# LED_s_Teclado2.net
KiCad netlist of a schematic drawn in Altium Designer
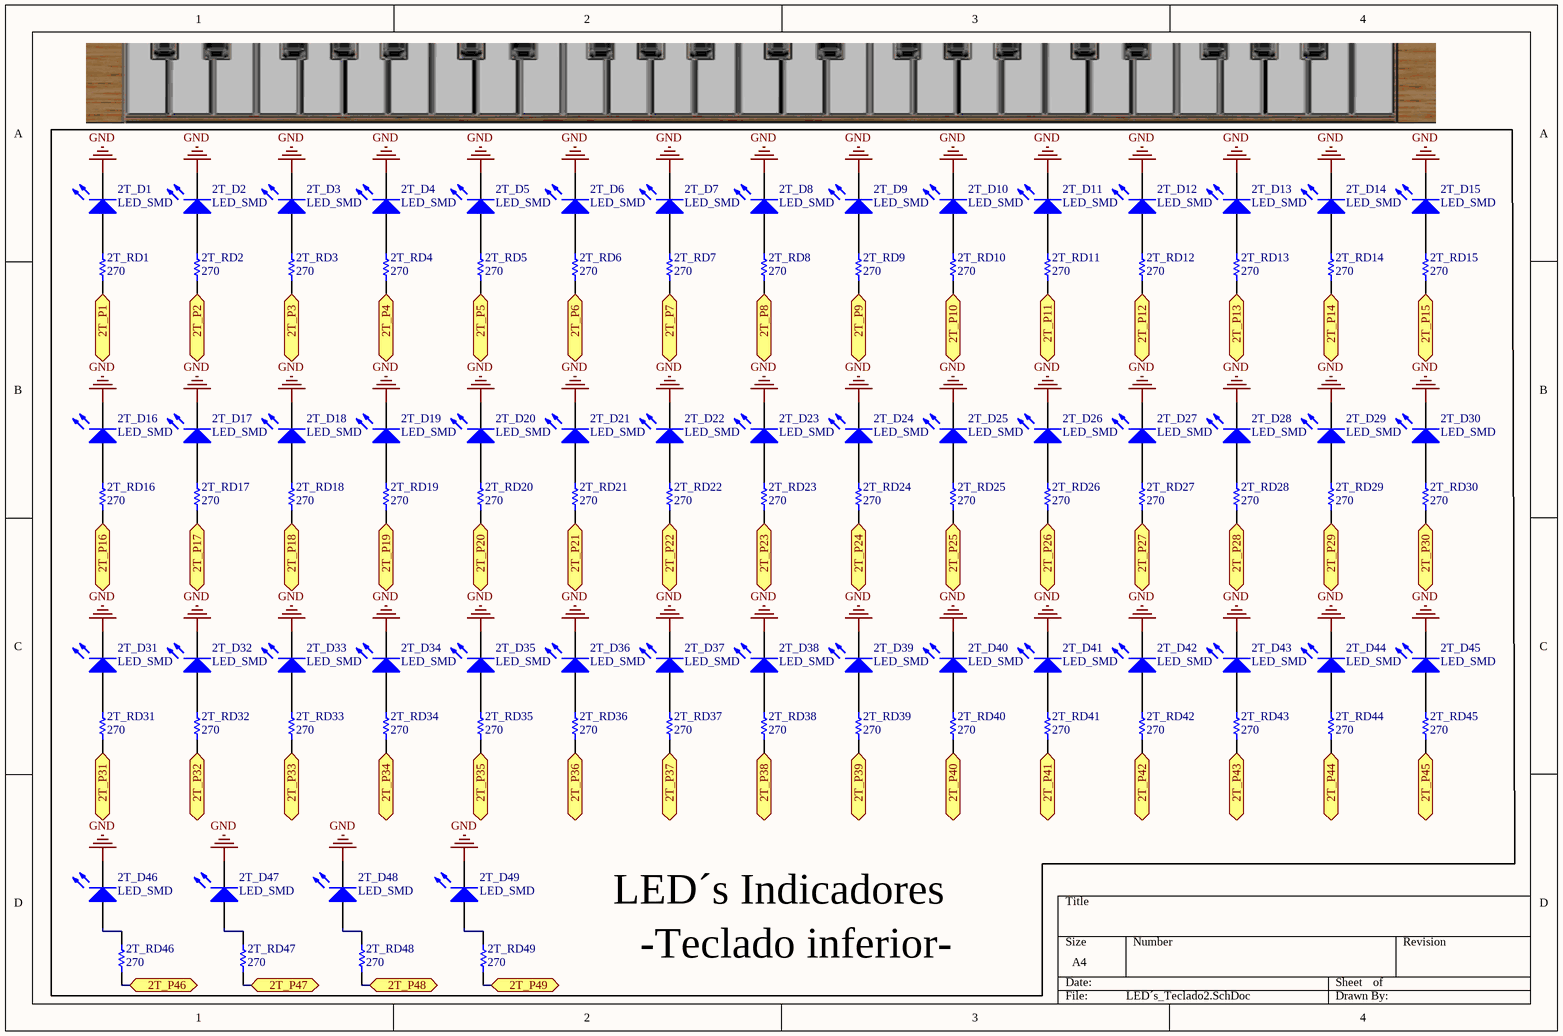
[diagram p0: LED´s_Teclado2.SchDoc]

(export (version "E")
  (design (tool "Eeschema 10.0.6"))
  (components
    (comp (ref "2T_D1")
      (value "LED_SMD")
      (footprint "0805")
      (description "LED SMD")
      (fields (field (name "PUBLISHER") "Altium Limited"))
      (libsource (lib "Libreria_Organo") (part "LED_SMD"))
    )
    (comp (ref "2T_D2")
      (value "LED_SMD")
      (footprint "0805")
      (description "LED SMD")
      (fields (field (name "PUBLISHER") "Altium Limited"))
      (libsource (lib "Libreria_Organo") (part "LED_SMD"))
    )
    (comp (ref "2T_D3")
      (value "LED_SMD")
      (footprint "0805")
      (description "LED SMD")
      (fields (field (name "PUBLISHER") "Altium Limited"))
      (libsource (lib "Libreria_Organo") (part "LED_SMD"))
    )
    (comp (ref "2T_D4")
      (value "LED_SMD")
      (footprint "0805")
      (description "LED SMD")
      (fields (field (name "PUBLISHER") "Altium Limited"))
      (libsource (lib "Libreria_Organo") (part "LED_SMD"))
    )
    (comp (ref "2T_D5")
      (value "LED_SMD")
      (footprint "0805")
      (description "LED SMD")
      (fields (field (name "PUBLISHER") "Altium Limited"))
      (libsource (lib "Libreria_Organo") (part "LED_SMD"))
    )
    (comp (ref "2T_D6")
      (value "LED_SMD")
      (footprint "0805")
      (description "LED SMD")
      (fields (field (name "PUBLISHER") "Altium Limited"))
      (libsource (lib "Libreria_Organo") (part "LED_SMD"))
    )
    (comp (ref "2T_D7")
      (value "LED_SMD")
      (footprint "0805")
      (description "LED SMD")
      (fields (field (name "PUBLISHER") "Altium Limited"))
      (libsource (lib "Libreria_Organo") (part "LED_SMD"))
    )
    (comp (ref "2T_D8")
      (value "LED_SMD")
      (footprint "0805")
      (description "LED SMD")
      (fields (field (name "PUBLISHER") "Altium Limited"))
      (libsource (lib "Libreria_Organo") (part "LED_SMD"))
    )
    (comp (ref "2T_D9")
      (value "LED_SMD")
      (footprint "0805")
      (description "LED SMD")
      (fields (field (name "PUBLISHER") "Altium Limited"))
      (libsource (lib "Libreria_Organo") (part "LED_SMD"))
    )
    (comp (ref "2T_D10")
      (value "LED_SMD")
      (footprint "0805")
      (description "LED SMD")
      (fields (field (name "PUBLISHER") "Altium Limited"))
      (libsource (lib "Libreria_Organo") (part "LED_SMD"))
    )
    (comp (ref "2T_D11")
      (value "LED_SMD")
      (footprint "0805")
      (description "LED SMD")
      (fields (field (name "PUBLISHER") "Altium Limited"))
      (libsource (lib "Libreria_Organo") (part "LED_SMD"))
    )
    (comp (ref "2T_D12")
      (value "LED_SMD")
      (footprint "0805")
      (description "LED SMD")
      (fields (field (name "PUBLISHER") "Altium Limited"))
      (libsource (lib "Libreria_Organo") (part "LED_SMD"))
    )
    (comp (ref "2T_D13")
      (value "LED_SMD")
      (footprint "0805")
      (description "LED SMD")
      (fields (field (name "PUBLISHER") "Altium Limited"))
      (libsource (lib "Libreria_Organo") (part "LED_SMD"))
    )
    (comp (ref "2T_D14")
      (value "LED_SMD")
      (footprint "0805")
      (description "LED SMD")
      (fields (field (name "PUBLISHER") "Altium Limited"))
      (libsource (lib "Libreria_Organo") (part "LED_SMD"))
    )
    (comp (ref "2T_D15")
      (value "LED_SMD")
      (footprint "0805")
      (description "LED SMD")
      (fields (field (name "PUBLISHER") "Altium Limited"))
      (libsource (lib "Libreria_Organo") (part "LED_SMD"))
    )
    (comp (ref "2T_D16")
      (value "LED_SMD")
      (footprint "0805")
      (description "LED SMD")
      (fields (field (name "PUBLISHER") "Altium Limited"))
      (libsource (lib "Libreria_Organo") (part "LED_SMD"))
    )
    (comp (ref "2T_D17")
      (value "LED_SMD")
      (footprint "0805")
      (description "LED SMD")
      (fields (field (name "PUBLISHER") "Altium Limited"))
      (libsource (lib "Libreria_Organo") (part "LED_SMD"))
    )
    (comp (ref "2T_D18")
      (value "LED_SMD")
      (footprint "0805")
      (description "LED SMD")
      (fields (field (name "PUBLISHER") "Altium Limited"))
      (libsource (lib "Libreria_Organo") (part "LED_SMD"))
    )
    (comp (ref "2T_D19")
      (value "LED_SMD")
      (footprint "0805")
      (description "LED SMD")
      (fields (field (name "PUBLISHER") "Altium Limited"))
      (libsource (lib "Libreria_Organo") (part "LED_SMD"))
    )
    (comp (ref "2T_D20")
      (value "LED_SMD")
      (footprint "0805")
      (description "LED SMD")
      (fields (field (name "PUBLISHER") "Altium Limited"))
      (libsource (lib "Libreria_Organo") (part "LED_SMD"))
    )
    (comp (ref "2T_D21")
      (value "LED_SMD")
      (footprint "0805")
      (description "LED SMD")
      (fields (field (name "PUBLISHER") "Altium Limited"))
      (libsource (lib "Libreria_Organo") (part "LED_SMD"))
    )
    (comp (ref "2T_D22")
      (value "LED_SMD")
      (footprint "0805")
      (description "LED SMD")
      (fields (field (name "PUBLISHER") "Altium Limited"))
      (libsource (lib "Libreria_Organo") (part "LED_SMD"))
    )
    (comp (ref "2T_D23")
      (value "LED_SMD")
      (footprint "0805")
      (description "LED SMD")
      (fields (field (name "PUBLISHER") "Altium Limited"))
      (libsource (lib "Libreria_Organo") (part "LED_SMD"))
    )
    (comp (ref "2T_D24")
      (value "LED_SMD")
      (footprint "0805")
      (description "LED SMD")
      (fields (field (name "PUBLISHER") "Altium Limited"))
      (libsource (lib "Libreria_Organo") (part "LED_SMD"))
    )
    (comp (ref "2T_D25")
      (value "LED_SMD")
      (footprint "0805")
      (description "LED SMD")
      (fields (field (name "PUBLISHER") "Altium Limited"))
      (libsource (lib "Libreria_Organo") (part "LED_SMD"))
    )
    (comp (ref "2T_D26")
      (value "LED_SMD")
      (footprint "0805")
      (description "LED SMD")
      (fields (field (name "PUBLISHER") "Altium Limited"))
      (libsource (lib "Libreria_Organo") (part "LED_SMD"))
    )
    (comp (ref "2T_D27")
      (value "LED_SMD")
      (footprint "0805")
      (description "LED SMD")
      (fields (field (name "PUBLISHER") "Altium Limited"))
      (libsource (lib "Libreria_Organo") (part "LED_SMD"))
    )
    (comp (ref "2T_D28")
      (value "LED_SMD")
      (footprint "0805")
      (description "LED SMD")
      (fields (field (name "PUBLISHER") "Altium Limited"))
      (libsource (lib "Libreria_Organo") (part "LED_SMD"))
    )
    (comp (ref "2T_D29")
      (value "LED_SMD")
      (footprint "0805")
      (description "LED SMD")
      (fields (field (name "PUBLISHER") "Altium Limited"))
      (libsource (lib "Libreria_Organo") (part "LED_SMD"))
    )
    (comp (ref "2T_D30")
      (value "LED_SMD")
      (footprint "0805")
      (description "LED SMD")
      (fields (field (name "PUBLISHER") "Altium Limited"))
      (libsource (lib "Libreria_Organo") (part "LED_SMD"))
    )
    (comp (ref "2T_D31")
      (value "LED_SMD")
      (footprint "0805")
      (description "LED SMD")
      (fields (field (name "PUBLISHER") "Altium Limited"))
      (libsource (lib "Libreria_Organo") (part "LED_SMD"))
    )
    (comp (ref "2T_D32")
      (value "LED_SMD")
      (footprint "0805")
      (description "LED SMD")
      (fields (field (name "PUBLISHER") "Altium Limited"))
      (libsource (lib "Libreria_Organo") (part "LED_SMD"))
    )
    (comp (ref "2T_D33")
      (value "LED_SMD")
      (footprint "0805")
      (description "LED SMD")
      (fields (field (name "PUBLISHER") "Altium Limited"))
      (libsource (lib "Libreria_Organo") (part "LED_SMD"))
    )
    (comp (ref "2T_D34")
      (value "LED_SMD")
      (footprint "0805")
      (description "LED SMD")
      (fields (field (name "PUBLISHER") "Altium Limited"))
      (libsource (lib "Libreria_Organo") (part "LED_SMD"))
    )
    (comp (ref "2T_D35")
      (value "LED_SMD")
      (footprint "0805")
      (description "LED SMD")
      (fields (field (name "PUBLISHER") "Altium Limited"))
      (libsource (lib "Libreria_Organo") (part "LED_SMD"))
    )
    (comp (ref "2T_D36")
      (value "LED_SMD")
      (footprint "0805")
      (description "LED SMD")
      (fields (field (name "PUBLISHER") "Altium Limited"))
      (libsource (lib "Libreria_Organo") (part "LED_SMD"))
    )
    (comp (ref "2T_D37")
      (value "LED_SMD")
      (footprint "0805")
      (description "LED SMD")
      (fields (field (name "PUBLISHER") "Altium Limited"))
      (libsource (lib "Libreria_Organo") (part "LED_SMD"))
    )
    (comp (ref "2T_D38")
      (value "LED_SMD")
      (footprint "0805")
      (description "LED SMD")
      (fields (field (name "PUBLISHER") "Altium Limited"))
      (libsource (lib "Libreria_Organo") (part "LED_SMD"))
    )
    (comp (ref "2T_D39")
      (value "LED_SMD")
      (footprint "0805")
      (description "LED SMD")
      (fields (field (name "PUBLISHER") "Altium Limited"))
      (libsource (lib "Libreria_Organo") (part "LED_SMD"))
    )
    (comp (ref "2T_D40")
      (value "LED_SMD")
      (footprint "0805")
      (description "LED SMD")
      (fields (field (name "PUBLISHER") "Altium Limited"))
      (libsource (lib "Libreria_Organo") (part "LED_SMD"))
    )
    (comp (ref "2T_D41")
      (value "LED_SMD")
      (footprint "0805")
      (description "LED SMD")
      (fields (field (name "PUBLISHER") "Altium Limited"))
      (libsource (lib "Libreria_Organo") (part "LED_SMD"))
    )
    (comp (ref "2T_D42")
      (value "LED_SMD")
      (footprint "0805")
      (description "LED SMD")
      (fields (field (name "PUBLISHER") "Altium Limited"))
      (libsource (lib "Libreria_Organo") (part "LED_SMD"))
    )
    (comp (ref "2T_D43")
      (value "LED_SMD")
      (footprint "0805")
      (description "LED SMD")
      (fields (field (name "PUBLISHER") "Altium Limited"))
      (libsource (lib "Libreria_Organo") (part "LED_SMD"))
    )
    (comp (ref "2T_D44")
      (value "LED_SMD")
      (footprint "0805")
      (description "LED SMD")
      (fields (field (name "PUBLISHER") "Altium Limited"))
      (libsource (lib "Libreria_Organo") (part "LED_SMD"))
    )
    (comp (ref "2T_D45")
      (value "LED_SMD")
      (footprint "0805")
      (description "LED SMD")
      (fields (field (name "PUBLISHER") "Altium Limited"))
      (libsource (lib "Libreria_Organo") (part "LED_SMD"))
    )
    (comp (ref "2T_D46")
      (value "LED_SMD")
      (footprint "0805")
      (description "LED SMD")
      (fields (field (name "PUBLISHER") "Altium Limited"))
      (libsource (lib "Libreria_Organo") (part "LED_SMD"))
    )
    (comp (ref "2T_D47")
      (value "LED_SMD")
      (footprint "0805")
      (description "LED SMD")
      (fields (field (name "PUBLISHER") "Altium Limited"))
      (libsource (lib "Libreria_Organo") (part "LED_SMD"))
    )
    (comp (ref "2T_D48")
      (value "LED_SMD")
      (footprint "0805")
      (description "LED SMD")
      (fields (field (name "PUBLISHER") "Altium Limited"))
      (libsource (lib "Libreria_Organo") (part "LED_SMD"))
    )
    (comp (ref "2T_D49")
      (value "LED_SMD")
      (footprint "0805")
      (description "LED SMD")
      (fields (field (name "PUBLISHER") "Altium Limited"))
      (libsource (lib "Libreria_Organo") (part "LED_SMD"))
    )
    (comp (ref "2T_RD1")
      (value "270")
      (footprint "0805 Chip Res")
      (description "Res Chip 0805")
      (fields (field (name "PUBLISHER") "Altium Limited"))
      (libsource (lib "Libreria_Organo") (part "Resistencia"))
    )
    (comp (ref "2T_RD2")
      (value "270")
      (footprint "0805 Chip Res")
      (description "Res Chip 0805")
      (fields (field (name "PUBLISHER") "Altium Limited"))
      (libsource (lib "Libreria_Organo") (part "Resistencia"))
    )
    (comp (ref "2T_RD3")
      (value "270")
      (footprint "0805 Chip Res")
      (description "Res Chip 0805")
      (fields (field (name "PUBLISHER") "Altium Limited"))
      (libsource (lib "Libreria_Organo") (part "Resistencia"))
    )
    (comp (ref "2T_RD4")
      (value "270")
      (footprint "0805 Chip Res")
      (description "Res Chip 0805")
      (fields (field (name "PUBLISHER") "Altium Limited"))
      (libsource (lib "Libreria_Organo") (part "Resistencia"))
    )
    (comp (ref "2T_RD5")
      (value "270")
      (footprint "0805 Chip Res")
      (description "Res Chip 0805")
      (fields (field (name "PUBLISHER") "Altium Limited"))
      (libsource (lib "Libreria_Organo") (part "Resistencia"))
    )
    (comp (ref "2T_RD6")
      (value "270")
      (footprint "0805 Chip Res")
      (description "Res Chip 0805")
      (fields (field (name "PUBLISHER") "Altium Limited"))
      (libsource (lib "Libreria_Organo") (part "Resistencia"))
    )
    (comp (ref "2T_RD7")
      (value "270")
      (footprint "0805 Chip Res")
      (description "Res Chip 0805")
      (fields (field (name "PUBLISHER") "Altium Limited"))
      (libsource (lib "Libreria_Organo") (part "Resistencia"))
    )
    (comp (ref "2T_RD8")
      (value "270")
      (footprint "0805 Chip Res")
      (description "Res Chip 0805")
      (fields (field (name "PUBLISHER") "Altium Limited"))
      (libsource (lib "Libreria_Organo") (part "Resistencia"))
    )
    (comp (ref "2T_RD9")
      (value "270")
      (footprint "0805 Chip Res")
      (description "Res Chip 0805")
      (fields (field (name "PUBLISHER") "Altium Limited"))
      (libsource (lib "Libreria_Organo") (part "Resistencia"))
    )
    (comp (ref "2T_RD10")
      (value "270")
      (footprint "0805 Chip Res")
      (description "Res Chip 0805")
      (fields (field (name "PUBLISHER") "Altium Limited"))
      (libsource (lib "Libreria_Organo") (part "Resistencia"))
    )
    (comp (ref "2T_RD11")
      (value "270")
      (footprint "0805 Chip Res")
      (description "Res Chip 0805")
      (fields (field (name "PUBLISHER") "Altium Limited"))
      (libsource (lib "Libreria_Organo") (part "Resistencia"))
    )
    (comp (ref "2T_RD12")
      (value "270")
      (footprint "0805 Chip Res")
      (description "Res Chip 0805")
      (fields (field (name "PUBLISHER") "Altium Limited"))
      (libsource (lib "Libreria_Organo") (part "Resistencia"))
    )
    (comp (ref "2T_RD13")
      (value "270")
      (footprint "0805 Chip Res")
      (description "Res Chip 0805")
      (fields (field (name "PUBLISHER") "Altium Limited"))
      (libsource (lib "Libreria_Organo") (part "Resistencia"))
    )
    (comp (ref "2T_RD14")
      (value "270")
      (footprint "0805 Chip Res")
      (description "Res Chip 0805")
      (fields (field (name "PUBLISHER") "Altium Limited"))
      (libsource (lib "Libreria_Organo") (part "Resistencia"))
    )
    (comp (ref "2T_RD15")
      (value "270")
      (footprint "0805 Chip Res")
      (description "Res Chip 0805")
      (fields (field (name "PUBLISHER") "Altium Limited"))
      (libsource (lib "Libreria_Organo") (part "Resistencia"))
    )
    (comp (ref "2T_RD16")
      (value "270")
      (footprint "0805 Chip Res")
      (description "Res Chip 0805")
      (fields (field (name "PUBLISHER") "Altium Limited"))
      (libsource (lib "Libreria_Organo") (part "Resistencia"))
    )
    (comp (ref "2T_RD17")
      (value "270")
      (footprint "0805 Chip Res")
      (description "Res Chip 0805")
      (fields (field (name "PUBLISHER") "Altium Limited"))
      (libsource (lib "Libreria_Organo") (part "Resistencia"))
    )
    (comp (ref "2T_RD18")
      (value "270")
      (footprint "0805 Chip Res")
      (description "Res Chip 0805")
      (fields (field (name "PUBLISHER") "Altium Limited"))
      (libsource (lib "Libreria_Organo") (part "Resistencia"))
    )
    (comp (ref "2T_RD19")
      (value "270")
      (footprint "0805 Chip Res")
      (description "Res Chip 0805")
      (fields (field (name "PUBLISHER") "Altium Limited"))
      (libsource (lib "Libreria_Organo") (part "Resistencia"))
    )
    (comp (ref "2T_RD20")
      (value "270")
      (footprint "0805 Chip Res")
      (description "Res Chip 0805")
      (fields (field (name "PUBLISHER") "Altium Limited"))
      (libsource (lib "Libreria_Organo") (part "Resistencia"))
    )
    (comp (ref "2T_RD21")
      (value "270")
      (footprint "0805 Chip Res")
      (description "Res Chip 0805")
      (fields (field (name "PUBLISHER") "Altium Limited"))
      (libsource (lib "Libreria_Organo") (part "Resistencia"))
    )
    (comp (ref "2T_RD22")
      (value "270")
      (footprint "0805 Chip Res")
      (description "Res Chip 0805")
      (fields (field (name "PUBLISHER") "Altium Limited"))
      (libsource (lib "Libreria_Organo") (part "Resistencia"))
    )
    (comp (ref "2T_RD23")
      (value "270")
      (footprint "0805 Chip Res")
      (description "Res Chip 0805")
      (fields (field (name "PUBLISHER") "Altium Limited"))
      (libsource (lib "Libreria_Organo") (part "Resistencia"))
    )
    (comp (ref "2T_RD24")
      (value "270")
      (footprint "0805 Chip Res")
      (description "Res Chip 0805")
      (fields (field (name "PUBLISHER") "Altium Limited"))
      (libsource (lib "Libreria_Organo") (part "Resistencia"))
    )
    (comp (ref "2T_RD25")
      (value "270")
      (footprint "0805 Chip Res")
      (description "Res Chip 0805")
      (fields (field (name "PUBLISHER") "Altium Limited"))
      (libsource (lib "Libreria_Organo") (part "Resistencia"))
    )
    (comp (ref "2T_RD26")
      (value "270")
      (footprint "0805 Chip Res")
      (description "Res Chip 0805")
      (fields (field (name "PUBLISHER") "Altium Limited"))
      (libsource (lib "Libreria_Organo") (part "Resistencia"))
    )
    (comp (ref "2T_RD27")
      (value "270")
      (footprint "0805 Chip Res")
      (description "Res Chip 0805")
      (fields (field (name "PUBLISHER") "Altium Limited"))
      (libsource (lib "Libreria_Organo") (part "Resistencia"))
    )
    (comp (ref "2T_RD28")
      (value "270")
      (footprint "0805 Chip Res")
      (description "Res Chip 0805")
      (fields (field (name "PUBLISHER") "Altium Limited"))
      (libsource (lib "Libreria_Organo") (part "Resistencia"))
    )
    (comp (ref "2T_RD29")
      (value "270")
      (footprint "0805 Chip Res")
      (description "Res Chip 0805")
      (fields (field (name "PUBLISHER") "Altium Limited"))
      (libsource (lib "Libreria_Organo") (part "Resistencia"))
    )
    (comp (ref "2T_RD30")
      (value "270")
      (footprint "0805 Chip Res")
      (description "Res Chip 0805")
      (fields (field (name "PUBLISHER") "Altium Limited"))
      (libsource (lib "Libreria_Organo") (part "Resistencia"))
    )
    (comp (ref "2T_RD31")
      (value "270")
      (footprint "0805 Chip Res")
      (description "Res Chip 0805")
      (fields (field (name "PUBLISHER") "Altium Limited"))
      (libsource (lib "Libreria_Organo") (part "Resistencia"))
    )
    (comp (ref "2T_RD32")
      (value "270")
      (footprint "0805 Chip Res")
      (description "Res Chip 0805")
      (fields (field (name "PUBLISHER") "Altium Limited"))
      (libsource (lib "Libreria_Organo") (part "Resistencia"))
    )
    (comp (ref "2T_RD33")
      (value "270")
      (footprint "0805 Chip Res")
      (description "Res Chip 0805")
      (fields (field (name "PUBLISHER") "Altium Limited"))
      (libsource (lib "Libreria_Organo") (part "Resistencia"))
    )
    (comp (ref "2T_RD34")
      (value "270")
      (footprint "0805 Chip Res")
      (description "Res Chip 0805")
      (fields (field (name "PUBLISHER") "Altium Limited"))
      (libsource (lib "Libreria_Organo") (part "Resistencia"))
    )
    (comp (ref "2T_RD35")
      (value "270")
      (footprint "0805 Chip Res")
      (description "Res Chip 0805")
      (fields (field (name "PUBLISHER") "Altium Limited"))
      (libsource (lib "Libreria_Organo") (part "Resistencia"))
    )
    (comp (ref "2T_RD36")
      (value "270")
      (footprint "0805 Chip Res")
      (description "Res Chip 0805")
      (fields (field (name "PUBLISHER") "Altium Limited"))
      (libsource (lib "Libreria_Organo") (part "Resistencia"))
    )
    (comp (ref "2T_RD37")
      (value "270")
      (footprint "0805 Chip Res")
      (description "Res Chip 0805")
      (fields (field (name "PUBLISHER") "Altium Limited"))
      (libsource (lib "Libreria_Organo") (part "Resistencia"))
    )
    (comp (ref "2T_RD38")
      (value "270")
      (footprint "0805 Chip Res")
      (description "Res Chip 0805")
      (fields (field (name "PUBLISHER") "Altium Limited"))
      (libsource (lib "Libreria_Organo") (part "Resistencia"))
    )
    (comp (ref "2T_RD39")
      (value "270")
      (footprint "0805 Chip Res")
      (description "Res Chip 0805")
      (fields (field (name "PUBLISHER") "Altium Limited"))
      (libsource (lib "Libreria_Organo") (part "Resistencia"))
    )
    (comp (ref "2T_RD40")
      (value "270")
      (footprint "0805 Chip Res")
      (description "Res Chip 0805")
      (fields (field (name "PUBLISHER") "Altium Limited"))
      (libsource (lib "Libreria_Organo") (part "Resistencia"))
    )
    (comp (ref "2T_RD41")
      (value "270")
      (footprint "0805 Chip Res")
      (description "Res Chip 0805")
      (fields (field (name "PUBLISHER") "Altium Limited"))
      (libsource (lib "Libreria_Organo") (part "Resistencia"))
    )
    (comp (ref "2T_RD42")
      (value "270")
      (footprint "0805 Chip Res")
      (description "Res Chip 0805")
      (fields (field (name "PUBLISHER") "Altium Limited"))
      (libsource (lib "Libreria_Organo") (part "Resistencia"))
    )
    (comp (ref "2T_RD43")
      (value "270")
      (footprint "0805 Chip Res")
      (description "Res Chip 0805")
      (fields (field (name "PUBLISHER") "Altium Limited"))
      (libsource (lib "Libreria_Organo") (part "Resistencia"))
    )
    (comp (ref "2T_RD44")
      (value "270")
      (footprint "0805 Chip Res")
      (description "Res Chip 0805")
      (fields (field (name "PUBLISHER") "Altium Limited"))
      (libsource (lib "Libreria_Organo") (part "Resistencia"))
    )
    (comp (ref "2T_RD45")
      (value "270")
      (footprint "0805 Chip Res")
      (description "Res Chip 0805")
      (fields (field (name "PUBLISHER") "Altium Limited"))
      (libsource (lib "Libreria_Organo") (part "Resistencia"))
    )
    (comp (ref "2T_RD46")
      (value "270")
      (footprint "0805 Chip Res")
      (description "Res Chip 0805")
      (fields (field (name "PUBLISHER") "Altium Limited"))
      (libsource (lib "Libreria_Organo") (part "Resistencia"))
    )
    (comp (ref "2T_RD47")
      (value "270")
      (footprint "0805 Chip Res")
      (description "Res Chip 0805")
      (fields (field (name "PUBLISHER") "Altium Limited"))
      (libsource (lib "Libreria_Organo") (part "Resistencia"))
    )
    (comp (ref "2T_RD48")
      (value "270")
      (footprint "0805 Chip Res")
      (description "Res Chip 0805")
      (fields (field (name "PUBLISHER") "Altium Limited"))
      (libsource (lib "Libreria_Organo") (part "Resistencia"))
    )
    (comp (ref "2T_RD49")
      (value "270")
      (footprint "0805 Chip Res")
      (description "Res Chip 0805")
      (fields (field (name "PUBLISHER") "Altium Limited"))
      (libsource (lib "Libreria_Organo") (part "Resistencia"))
    )
  )
  (nets
    (net (code "1") (name "/2T_P1") (class "Default")
      (node (ref "2T_RD1") (pin "1") (pinfunction "1_1") (pintype "passive"))
    )
    (net (code "2") (name "/2T_P2") (class "Default")
      (node (ref "2T_RD2") (pin "1") (pinfunction "1_1") (pintype "passive"))
    )
    (net (code "3") (name "/2T_P3") (class "Default")
      (node (ref "2T_RD3") (pin "1") (pinfunction "1_1") (pintype "passive"))
    )
    (net (code "4") (name "/2T_P4") (class "Default")
      (node (ref "2T_RD4") (pin "1") (pinfunction "1_1") (pintype "passive"))
    )
    (net (code "5") (name "/2T_P5") (class "Default")
      (node (ref "2T_RD5") (pin "1") (pinfunction "1_1") (pintype "passive"))
    )
    (net (code "6") (name "/2T_P6") (class "Default")
      (node (ref "2T_RD6") (pin "1") (pinfunction "1_1") (pintype "passive"))
    )
    (net (code "7") (name "/2T_P7") (class "Default")
      (node (ref "2T_RD7") (pin "1") (pinfunction "1_1") (pintype "passive"))
    )
    (net (code "8") (name "/2T_P8") (class "Default")
      (node (ref "2T_RD8") (pin "1") (pinfunction "1_1") (pintype "passive"))
    )
    (net (code "9") (name "/2T_P9") (class "Default")
      (node (ref "2T_RD9") (pin "1") (pinfunction "1_1") (pintype "passive"))
    )
    (net (code "10") (name "/2T_P10") (class "Default")
      (node (ref "2T_RD10") (pin "1") (pinfunction "1_1") (pintype "passive"))
    )
    (net (code "11") (name "/2T_P11") (class "Default")
      (node (ref "2T_RD11") (pin "1") (pinfunction "1_1") (pintype "passive"))
    )
    (net (code "12") (name "/2T_P12") (class "Default")
      (node (ref "2T_RD12") (pin "1") (pinfunction "1_1") (pintype "passive"))
    )
    (net (code "13") (name "/2T_P13") (class "Default")
      (node (ref "2T_RD13") (pin "1") (pinfunction "1_1") (pintype "passive"))
    )
    (net (code "14") (name "/2T_P14") (class "Default")
      (node (ref "2T_RD14") (pin "1") (pinfunction "1_1") (pintype "passive"))
    )
    (net (code "15") (name "/2T_P15") (class "Default")
      (node (ref "2T_RD15") (pin "1") (pinfunction "1_1") (pintype "passive"))
    )
    (net (code "16") (name "/2T_P16") (class "Default")
      (node (ref "2T_RD16") (pin "1") (pinfunction "1_1") (pintype "passive"))
    )
    (net (code "17") (name "/2T_P17") (class "Default")
      (node (ref "2T_RD17") (pin "1") (pinfunction "1_1") (pintype "passive"))
    )
    (net (code "18") (name "/2T_P18") (class "Default")
      (node (ref "2T_RD18") (pin "1") (pinfunction "1_1") (pintype "passive"))
    )
    (net (code "19") (name "/2T_P19") (class "Default")
      (node (ref "2T_RD19") (pin "1") (pinfunction "1_1") (pintype "passive"))
    )
    (net (code "20") (name "/2T_P20") (class "Default")
      (node (ref "2T_RD20") (pin "1") (pinfunction "1_1") (pintype "passive"))
    )
    (net (code "21") (name "/2T_P21") (class "Default")
      (node (ref "2T_RD21") (pin "1") (pinfunction "1_1") (pintype "passive"))
    )
    (net (code "22") (name "/2T_P22") (class "Default")
      (node (ref "2T_RD22") (pin "1") (pinfunction "1_1") (pintype "passive"))
    )
    (net (code "23") (name "/2T_P23") (class "Default")
      (node (ref "2T_RD23") (pin "1") (pinfunction "1_1") (pintype "passive"))
    )
    (net (code "24") (name "/2T_P24") (class "Default")
      (node (ref "2T_RD24") (pin "1") (pinfunction "1_1") (pintype "passive"))
    )
    (net (code "25") (name "/2T_P25") (class "Default")
      (node (ref "2T_RD25") (pin "1") (pinfunction "1_1") (pintype "passive"))
    )
    (net (code "26") (name "/2T_P26") (class "Default")
      (node (ref "2T_RD26") (pin "1") (pinfunction "1_1") (pintype "passive"))
    )
    (net (code "27") (name "/2T_P27") (class "Default")
      (node (ref "2T_RD27") (pin "1") (pinfunction "1_1") (pintype "passive"))
    )
    (net (code "28") (name "/2T_P28") (class "Default")
      (node (ref "2T_RD28") (pin "1") (pinfunction "1_1") (pintype "passive"))
    )
    (net (code "29") (name "/2T_P29") (class "Default")
      (node (ref "2T_RD29") (pin "1") (pinfunction "1_1") (pintype "passive"))
    )
    (net (code "30") (name "/2T_P30") (class "Default")
      (node (ref "2T_RD30") (pin "1") (pinfunction "1_1") (pintype "passive"))
    )
    (net (code "31") (name "/2T_P31") (class "Default")
      (node (ref "2T_RD31") (pin "1") (pinfunction "1_1") (pintype "passive"))
    )
    (net (code "32") (name "/2T_P32") (class "Default")
      (node (ref "2T_RD32") (pin "1") (pinfunction "1_1") (pintype "passive"))
    )
    (net (code "33") (name "/2T_P33") (class "Default")
      (node (ref "2T_RD33") (pin "1") (pinfunction "1_1") (pintype "passive"))
    )
    (net (code "34") (name "/2T_P34") (class "Default")
      (node (ref "2T_RD34") (pin "1") (pinfunction "1_1") (pintype "passive"))
    )
    (net (code "35") (name "/2T_P35") (class "Default")
      (node (ref "2T_RD35") (pin "1") (pinfunction "1_1") (pintype "passive"))
    )
    (net (code "36") (name "/2T_P36") (class "Default")
      (node (ref "2T_RD36") (pin "1") (pinfunction "1_1") (pintype "passive"))
    )
    (net (code "37") (name "/2T_P37") (class "Default")
      (node (ref "2T_RD37") (pin "1") (pinfunction "1_1") (pintype "passive"))
    )
    (net (code "38") (name "/2T_P38") (class "Default")
      (node (ref "2T_RD38") (pin "1") (pinfunction "1_1") (pintype "passive"))
    )
    (net (code "39") (name "/2T_P39") (class "Default")
      (node (ref "2T_RD39") (pin "1") (pinfunction "1_1") (pintype "passive"))
    )
    (net (code "40") (name "/2T_P40") (class "Default")
      (node (ref "2T_RD40") (pin "1") (pinfunction "1_1") (pintype "passive"))
    )
    (net (code "41") (name "/2T_P41") (class "Default")
      (node (ref "2T_RD41") (pin "1") (pinfunction "1_1") (pintype "passive"))
    )
    (net (code "42") (name "/2T_P42") (class "Default")
      (node (ref "2T_RD42") (pin "1") (pinfunction "1_1") (pintype "passive"))
    )
    (net (code "43") (name "/2T_P43") (class "Default")
      (node (ref "2T_RD43") (pin "1") (pinfunction "1_1") (pintype "passive"))
    )
    (net (code "44") (name "/2T_P44") (class "Default")
      (node (ref "2T_RD44") (pin "1") (pinfunction "1_1") (pintype "passive"))
    )
    (net (code "45") (name "/2T_P45") (class "Default")
      (node (ref "2T_RD45") (pin "1") (pinfunction "1_1") (pintype "passive"))
    )
    (net (code "46") (name "/2T_P46") (class "Default")
      (node (ref "2T_RD46") (pin "1") (pinfunction "1_1") (pintype "passive"))
    )
    (net (code "47") (name "/2T_P47") (class "Default")
      (node (ref "2T_RD47") (pin "1") (pinfunction "1_1") (pintype "passive"))
    )
    (net (code "48") (name "/2T_P48") (class "Default")
      (node (ref "2T_RD48") (pin "1") (pinfunction "1_1") (pintype "passive"))
    )
    (net (code "49") (name "/2T_P49") (class "Default")
      (node (ref "2T_RD49") (pin "1") (pinfunction "1_1") (pintype "passive"))
    )
    (net (code "50") (name "GND") (class "Default")
      (node (ref "2T_D1") (pin "2") (pinfunction "K_2") (pintype "passive"))
      (node (ref "2T_D10") (pin "2") (pinfunction "K_2") (pintype "passive"))
      (node (ref "2T_D11") (pin "2") (pinfunction "K_2") (pintype "passive"))
      (node (ref "2T_D12") (pin "2") (pinfunction "K_2") (pintype "passive"))
      (node (ref "2T_D13") (pin "2") (pinfunction "K_2") (pintype "passive"))
      (node (ref "2T_D14") (pin "2") (pinfunction "K_2") (pintype "passive"))
      (node (ref "2T_D15") (pin "2") (pinfunction "K_2") (pintype "passive"))
      (node (ref "2T_D16") (pin "2") (pinfunction "K_2") (pintype "passive"))
      (node (ref "2T_D17") (pin "2") (pinfunction "K_2") (pintype "passive"))
      (node (ref "2T_D18") (pin "2") (pinfunction "K_2") (pintype "passive"))
      (node (ref "2T_D19") (pin "2") (pinfunction "K_2") (pintype "passive"))
      (node (ref "2T_D2") (pin "2") (pinfunction "K_2") (pintype "passive"))
      (node (ref "2T_D20") (pin "2") (pinfunction "K_2") (pintype "passive"))
      (node (ref "2T_D21") (pin "2") (pinfunction "K_2") (pintype "passive"))
      (node (ref "2T_D22") (pin "2") (pinfunction "K_2") (pintype "passive"))
      (node (ref "2T_D23") (pin "2") (pinfunction "K_2") (pintype "passive"))
      (node (ref "2T_D24") (pin "2") (pinfunction "K_2") (pintype "passive"))
      (node (ref "2T_D25") (pin "2") (pinfunction "K_2") (pintype "passive"))
      (node (ref "2T_D26") (pin "2") (pinfunction "K_2") (pintype "passive"))
      (node (ref "2T_D27") (pin "2") (pinfunction "K_2") (pintype "passive"))
      (node (ref "2T_D28") (pin "2") (pinfunction "K_2") (pintype "passive"))
      (node (ref "2T_D29") (pin "2") (pinfunction "K_2") (pintype "passive"))
      (node (ref "2T_D3") (pin "2") (pinfunction "K_2") (pintype "passive"))
      (node (ref "2T_D30") (pin "2") (pinfunction "K_2") (pintype "passive"))
      (node (ref "2T_D31") (pin "2") (pinfunction "K_2") (pintype "passive"))
      (node (ref "2T_D32") (pin "2") (pinfunction "K_2") (pintype "passive"))
      (node (ref "2T_D33") (pin "2") (pinfunction "K_2") (pintype "passive"))
      (node (ref "2T_D34") (pin "2") (pinfunction "K_2") (pintype "passive"))
      (node (ref "2T_D35") (pin "2") (pinfunction "K_2") (pintype "passive"))
      (node (ref "2T_D36") (pin "2") (pinfunction "K_2") (pintype "passive"))
      (node (ref "2T_D37") (pin "2") (pinfunction "K_2") (pintype "passive"))
      (node (ref "2T_D38") (pin "2") (pinfunction "K_2") (pintype "passive"))
      (node (ref "2T_D39") (pin "2") (pinfunction "K_2") (pintype "passive"))
      (node (ref "2T_D4") (pin "2") (pinfunction "K_2") (pintype "passive"))
      (node (ref "2T_D40") (pin "2") (pinfunction "K_2") (pintype "passive"))
      (node (ref "2T_D41") (pin "2") (pinfunction "K_2") (pintype "passive"))
      (node (ref "2T_D42") (pin "2") (pinfunction "K_2") (pintype "passive"))
      (node (ref "2T_D43") (pin "2") (pinfunction "K_2") (pintype "passive"))
      (node (ref "2T_D44") (pin "2") (pinfunction "K_2") (pintype "passive"))
      (node (ref "2T_D45") (pin "2") (pinfunction "K_2") (pintype "passive"))
      (node (ref "2T_D46") (pin "2") (pinfunction "K_2") (pintype "passive"))
      (node (ref "2T_D47") (pin "2") (pinfunction "K_2") (pintype "passive"))
      (node (ref "2T_D48") (pin "2") (pinfunction "K_2") (pintype "passive"))
      (node (ref "2T_D49") (pin "2") (pinfunction "K_2") (pintype "passive"))
      (node (ref "2T_D5") (pin "2") (pinfunction "K_2") (pintype "passive"))
      (node (ref "2T_D6") (pin "2") (pinfunction "K_2") (pintype "passive"))
      (node (ref "2T_D7") (pin "2") (pinfunction "K_2") (pintype "passive"))
      (node (ref "2T_D8") (pin "2") (pinfunction "K_2") (pintype "passive"))
      (node (ref "2T_D9") (pin "2") (pinfunction "K_2") (pintype "passive"))
    )
    (net (code "51") (name "Net-(2T_D1-A)") (class "Default")
      (node (ref "2T_D1") (pin "1") (pinfunction "A_1") (pintype "passive"))
      (node (ref "2T_RD1") (pin "2") (pinfunction "2_2") (pintype "passive"))
    )
    (net (code "52") (name "Net-(2T_D2-A)") (class "Default")
      (node (ref "2T_D2") (pin "1") (pinfunction "A_1") (pintype "passive"))
      (node (ref "2T_RD2") (pin "2") (pinfunction "2_2") (pintype "passive"))
    )
    (net (code "53") (name "Net-(2T_D3-A)") (class "Default")
      (node (ref "2T_D3") (pin "1") (pinfunction "A_1") (pintype "passive"))
      (node (ref "2T_RD3") (pin "2") (pinfunction "2_2") (pintype "passive"))
    )
    (net (code "54") (name "Net-(2T_D4-A)") (class "Default")
      (node (ref "2T_D4") (pin "1") (pinfunction "A_1") (pintype "passive"))
      (node (ref "2T_RD4") (pin "2") (pinfunction "2_2") (pintype "passive"))
    )
    (net (code "55") (name "Net-(2T_D5-A)") (class "Default")
      (node (ref "2T_D5") (pin "1") (pinfunction "A_1") (pintype "passive"))
      (node (ref "2T_RD5") (pin "2") (pinfunction "2_2") (pintype "passive"))
    )
    (net (code "56") (name "Net-(2T_D6-A)") (class "Default")
      (node (ref "2T_D6") (pin "1") (pinfunction "A_1") (pintype "passive"))
      (node (ref "2T_RD6") (pin "2") (pinfunction "2_2") (pintype "passive"))
    )
    (net (code "57") (name "Net-(2T_D7-A)") (class "Default")
      (node (ref "2T_D7") (pin "1") (pinfunction "A_1") (pintype "passive"))
      (node (ref "2T_RD7") (pin "2") (pinfunction "2_2") (pintype "passive"))
    )
    (net (code "58") (name "Net-(2T_D8-A)") (class "Default")
      (node (ref "2T_D8") (pin "1") (pinfunction "A_1") (pintype "passive"))
      (node (ref "2T_RD8") (pin "2") (pinfunction "2_2") (pintype "passive"))
    )
    (net (code "59") (name "Net-(2T_D9-A)") (class "Default")
      (node (ref "2T_D9") (pin "1") (pinfunction "A_1") (pintype "passive"))
      (node (ref "2T_RD9") (pin "2") (pinfunction "2_2") (pintype "passive"))
    )
    (net (code "60") (name "Net-(2T_D10-A)") (class "Default")
      (node (ref "2T_D10") (pin "1") (pinfunction "A_1") (pintype "passive"))
      (node (ref "2T_RD10") (pin "2") (pinfunction "2_2") (pintype "passive"))
    )
    (net (code "61") (name "Net-(2T_D11-A)") (class "Default")
      (node (ref "2T_D11") (pin "1") (pinfunction "A_1") (pintype "passive"))
      (node (ref "2T_RD11") (pin "2") (pinfunction "2_2") (pintype "passive"))
    )
    (net (code "62") (name "Net-(2T_D12-A)") (class "Default")
      (node (ref "2T_D12") (pin "1") (pinfunction "A_1") (pintype "passive"))
      (node (ref "2T_RD12") (pin "2") (pinfunction "2_2") (pintype "passive"))
    )
    (net (code "63") (name "Net-(2T_D13-A)") (class "Default")
      (node (ref "2T_D13") (pin "1") (pinfunction "A_1") (pintype "passive"))
      (node (ref "2T_RD13") (pin "2") (pinfunction "2_2") (pintype "passive"))
    )
    (net (code "64") (name "Net-(2T_D14-A)") (class "Default")
      (node (ref "2T_D14") (pin "1") (pinfunction "A_1") (pintype "passive"))
      (node (ref "2T_RD14") (pin "2") (pinfunction "2_2") (pintype "passive"))
    )
    (net (code "65") (name "Net-(2T_D15-A)") (class "Default")
      (node (ref "2T_D15") (pin "1") (pinfunction "A_1") (pintype "passive"))
      (node (ref "2T_RD15") (pin "2") (pinfunction "2_2") (pintype "passive"))
    )
    (net (code "66") (name "Net-(2T_D16-A)") (class "Default")
      (node (ref "2T_D16") (pin "1") (pinfunction "A_1") (pintype "passive"))
      (node (ref "2T_RD16") (pin "2") (pinfunction "2_2") (pintype "passive"))
    )
    (net (code "67") (name "Net-(2T_D17-A)") (class "Default")
      (node (ref "2T_D17") (pin "1") (pinfunction "A_1") (pintype "passive"))
      (node (ref "2T_RD17") (pin "2") (pinfunction "2_2") (pintype "passive"))
    )
    (net (code "68") (name "Net-(2T_D18-A)") (class "Default")
      (node (ref "2T_D18") (pin "1") (pinfunction "A_1") (pintype "passive"))
      (node (ref "2T_RD18") (pin "2") (pinfunction "2_2") (pintype "passive"))
    )
    (net (code "69") (name "Net-(2T_D19-A)") (class "Default")
      (node (ref "2T_D19") (pin "1") (pinfunction "A_1") (pintype "passive"))
      (node (ref "2T_RD19") (pin "2") (pinfunction "2_2") (pintype "passive"))
    )
    (net (code "70") (name "Net-(2T_D20-A)") (class "Default")
      (node (ref "2T_D20") (pin "1") (pinfunction "A_1") (pintype "passive"))
      (node (ref "2T_RD20") (pin "2") (pinfunction "2_2") (pintype "passive"))
    )
    (net (code "71") (name "Net-(2T_D21-A)") (class "Default")
      (node (ref "2T_D21") (pin "1") (pinfunction "A_1") (pintype "passive"))
      (node (ref "2T_RD21") (pin "2") (pinfunction "2_2") (pintype "passive"))
    )
    (net (code "72") (name "Net-(2T_D22-A)") (class "Default")
      (node (ref "2T_D22") (pin "1") (pinfunction "A_1") (pintype "passive"))
      (node (ref "2T_RD22") (pin "2") (pinfunction "2_2") (pintype "passive"))
    )
    (net (code "73") (name "Net-(2T_D23-A)") (class "Default")
      (node (ref "2T_D23") (pin "1") (pinfunction "A_1") (pintype "passive"))
      (node (ref "2T_RD23") (pin "2") (pinfunction "2_2") (pintype "passive"))
    )
    (net (code "74") (name "Net-(2T_D24-A)") (class "Default")
      (node (ref "2T_D24") (pin "1") (pinfunction "A_1") (pintype "passive"))
      (node (ref "2T_RD24") (pin "2") (pinfunction "2_2") (pintype "passive"))
    )
    (net (code "75") (name "Net-(2T_D25-A)") (class "Default")
      (node (ref "2T_D25") (pin "1") (pinfunction "A_1") (pintype "passive"))
      (node (ref "2T_RD25") (pin "2") (pinfunction "2_2") (pintype "passive"))
    )
    (net (code "76") (name "Net-(2T_D26-A)") (class "Default")
      (node (ref "2T_D26") (pin "1") (pinfunction "A_1") (pintype "passive"))
      (node (ref "2T_RD26") (pin "2") (pinfunction "2_2") (pintype "passive"))
    )
    (net (code "77") (name "Net-(2T_D27-A)") (class "Default")
      (node (ref "2T_D27") (pin "1") (pinfunction "A_1") (pintype "passive"))
      (node (ref "2T_RD27") (pin "2") (pinfunction "2_2") (pintype "passive"))
    )
    (net (code "78") (name "Net-(2T_D28-A)") (class "Default")
      (node (ref "2T_D28") (pin "1") (pinfunction "A_1") (pintype "passive"))
      (node (ref "2T_RD28") (pin "2") (pinfunction "2_2") (pintype "passive"))
    )
    (net (code "79") (name "Net-(2T_D29-A)") (class "Default")
      (node (ref "2T_D29") (pin "1") (pinfunction "A_1") (pintype "passive"))
      (node (ref "2T_RD29") (pin "2") (pinfunction "2_2") (pintype "passive"))
    )
    (net (code "80") (name "Net-(2T_D30-A)") (class "Default")
      (node (ref "2T_D30") (pin "1") (pinfunction "A_1") (pintype "passive"))
      (node (ref "2T_RD30") (pin "2") (pinfunction "2_2") (pintype "passive"))
    )
    (net (code "81") (name "Net-(2T_D31-A)") (class "Default")
      (node (ref "2T_D31") (pin "1") (pinfunction "A_1") (pintype "passive"))
      (node (ref "2T_RD31") (pin "2") (pinfunction "2_2") (pintype "passive"))
    )
    (net (code "82") (name "Net-(2T_D32-A)") (class "Default")
      (node (ref "2T_D32") (pin "1") (pinfunction "A_1") (pintype "passive"))
      (node (ref "2T_RD32") (pin "2") (pinfunction "2_2") (pintype "passive"))
    )
    (net (code "83") (name "Net-(2T_D33-A)") (class "Default")
      (node (ref "2T_D33") (pin "1") (pinfunction "A_1") (pintype "passive"))
      (node (ref "2T_RD33") (pin "2") (pinfunction "2_2") (pintype "passive"))
    )
    (net (code "84") (name "Net-(2T_D34-A)") (class "Default")
      (node (ref "2T_D34") (pin "1") (pinfunction "A_1") (pintype "passive"))
      (node (ref "2T_RD34") (pin "2") (pinfunction "2_2") (pintype "passive"))
    )
    (net (code "85") (name "Net-(2T_D35-A)") (class "Default")
      (node (ref "2T_D35") (pin "1") (pinfunction "A_1") (pintype "passive"))
      (node (ref "2T_RD35") (pin "2") (pinfunction "2_2") (pintype "passive"))
    )
    (net (code "86") (name "Net-(2T_D36-A)") (class "Default")
      (node (ref "2T_D36") (pin "1") (pinfunction "A_1") (pintype "passive"))
      (node (ref "2T_RD36") (pin "2") (pinfunction "2_2") (pintype "passive"))
    )
    (net (code "87") (name "Net-(2T_D37-A)") (class "Default")
      (node (ref "2T_D37") (pin "1") (pinfunction "A_1") (pintype "passive"))
      (node (ref "2T_RD37") (pin "2") (pinfunction "2_2") (pintype "passive"))
    )
    (net (code "88") (name "Net-(2T_D38-A)") (class "Default")
      (node (ref "2T_D38") (pin "1") (pinfunction "A_1") (pintype "passive"))
      (node (ref "2T_RD38") (pin "2") (pinfunction "2_2") (pintype "passive"))
    )
    (net (code "89") (name "Net-(2T_D39-A)") (class "Default")
      (node (ref "2T_D39") (pin "1") (pinfunction "A_1") (pintype "passive"))
      (node (ref "2T_RD39") (pin "2") (pinfunction "2_2") (pintype "passive"))
    )
    (net (code "90") (name "Net-(2T_D40-A)") (class "Default")
      (node (ref "2T_D40") (pin "1") (pinfunction "A_1") (pintype "passive"))
      (node (ref "2T_RD40") (pin "2") (pinfunction "2_2") (pintype "passive"))
    )
    (net (code "91") (name "Net-(2T_D41-A)") (class "Default")
      (node (ref "2T_D41") (pin "1") (pinfunction "A_1") (pintype "passive"))
      (node (ref "2T_RD41") (pin "2") (pinfunction "2_2") (pintype "passive"))
    )
    (net (code "92") (name "Net-(2T_D42-A)") (class "Default")
      (node (ref "2T_D42") (pin "1") (pinfunction "A_1") (pintype "passive"))
      (node (ref "2T_RD42") (pin "2") (pinfunction "2_2") (pintype "passive"))
    )
    (net (code "93") (name "Net-(2T_D43-A)") (class "Default")
      (node (ref "2T_D43") (pin "1") (pinfunction "A_1") (pintype "passive"))
      (node (ref "2T_RD43") (pin "2") (pinfunction "2_2") (pintype "passive"))
    )
    (net (code "94") (name "Net-(2T_D44-A)") (class "Default")
      (node (ref "2T_D44") (pin "1") (pinfunction "A_1") (pintype "passive"))
      (node (ref "2T_RD44") (pin "2") (pinfunction "2_2") (pintype "passive"))
    )
    (net (code "95") (name "Net-(2T_D45-A)") (class "Default")
      (node (ref "2T_D45") (pin "1") (pinfunction "A_1") (pintype "passive"))
      (node (ref "2T_RD45") (pin "2") (pinfunction "2_2") (pintype "passive"))
    )
    (net (code "96") (name "Net-(2T_D46-A)") (class "Default")
      (node (ref "2T_D46") (pin "1") (pinfunction "A_1") (pintype "passive"))
      (node (ref "2T_RD46") (pin "2") (pinfunction "2_2") (pintype "passive"))
    )
    (net (code "97") (name "Net-(2T_D47-A)") (class "Default")
      (node (ref "2T_D47") (pin "1") (pinfunction "A_1") (pintype "passive"))
      (node (ref "2T_RD47") (pin "2") (pinfunction "2_2") (pintype "passive"))
    )
    (net (code "98") (name "Net-(2T_D48-A)") (class "Default")
      (node (ref "2T_D48") (pin "1") (pinfunction "A_1") (pintype "passive"))
      (node (ref "2T_RD48") (pin "2") (pinfunction "2_2") (pintype "passive"))
    )
    (net (code "99") (name "Net-(2T_D49-A)") (class "Default")
      (node (ref "2T_D49") (pin "1") (pinfunction "A_1") (pintype "passive"))
      (node (ref "2T_RD49") (pin "2") (pinfunction "2_2") (pintype "passive"))
    )
  )
)
